# ArduSensor-Knock.net
KiCad netlist of a schematic drawn in EAGLE
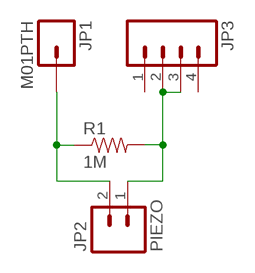
[diagram p0: schematic, sheet 1]

(export (version "E")
  (design (tool "Eeschema 10.0.6"))
  (components
    (comp (ref "JP1")
      (value "M01PTH")
      (footprint "eagle-import:1X01")
      (libsource (lib "eagle-import") (part "M01PTH"))
    )
    (comp (ref "JP2")
      (value "PIEZO")
      (footprint "eagle-import:1X02")
      (libsource (lib "eagle-import") (part "M02PTH"))
    )
    (comp (ref "JP3")
      (value "M04PTH")
      (footprint "eagle-import:1X04")
      (libsource (lib "eagle-import") (part "M04PTH"))
    )
    (comp (ref "R1")
      (value "1M")
      (footprint "eagle-import:AXIAL-0.3")
      (libsource (lib "eagle-import") (part "RESISTORAXIAL-0.3"))
    )
  )
  (nets
    (net (code "1") (name "Net-(R1-1)") (class "Default")
      (node (ref "JP1") (pin "1") (pinfunction "1_1") (pintype "passive"))
      (node (ref "JP2") (pin "2") (pinfunction "2_2") (pintype "passive"))
      (node (ref "R1") (pin "P$1") (pinfunction "1_P$1") (pintype "passive"))
    )
    (net (code "2") (name "Net-(R1-2)") (class "Default")
      (node (ref "JP2") (pin "1") (pinfunction "1_1") (pintype "passive"))
      (node (ref "JP3") (pin "2") (pinfunction "2_2") (pintype "passive"))
      (node (ref "JP3") (pin "3") (pinfunction "3_3") (pintype "passive"))
      (node (ref "R1") (pin "P$2") (pinfunction "2_P$2") (pintype "passive"))
    )
    (net (code "3") (name "unconnected-(JP3-Pad1)") (class "Default")
      (node (ref "JP3") (pin "1") (pinfunction "1_1") (pintype "passive"))
    )
    (net (code "4") (name "unconnected-(JP3-Pad4)") (class "Default")
      (node (ref "JP3") (pin "4") (pinfunction "4_4") (pintype "passive"))
    )
  )
)
